# 1-Schematic_STM32F103RCCoreBoard.net
KiCad netlist of a schematic drawn in EasyEDA
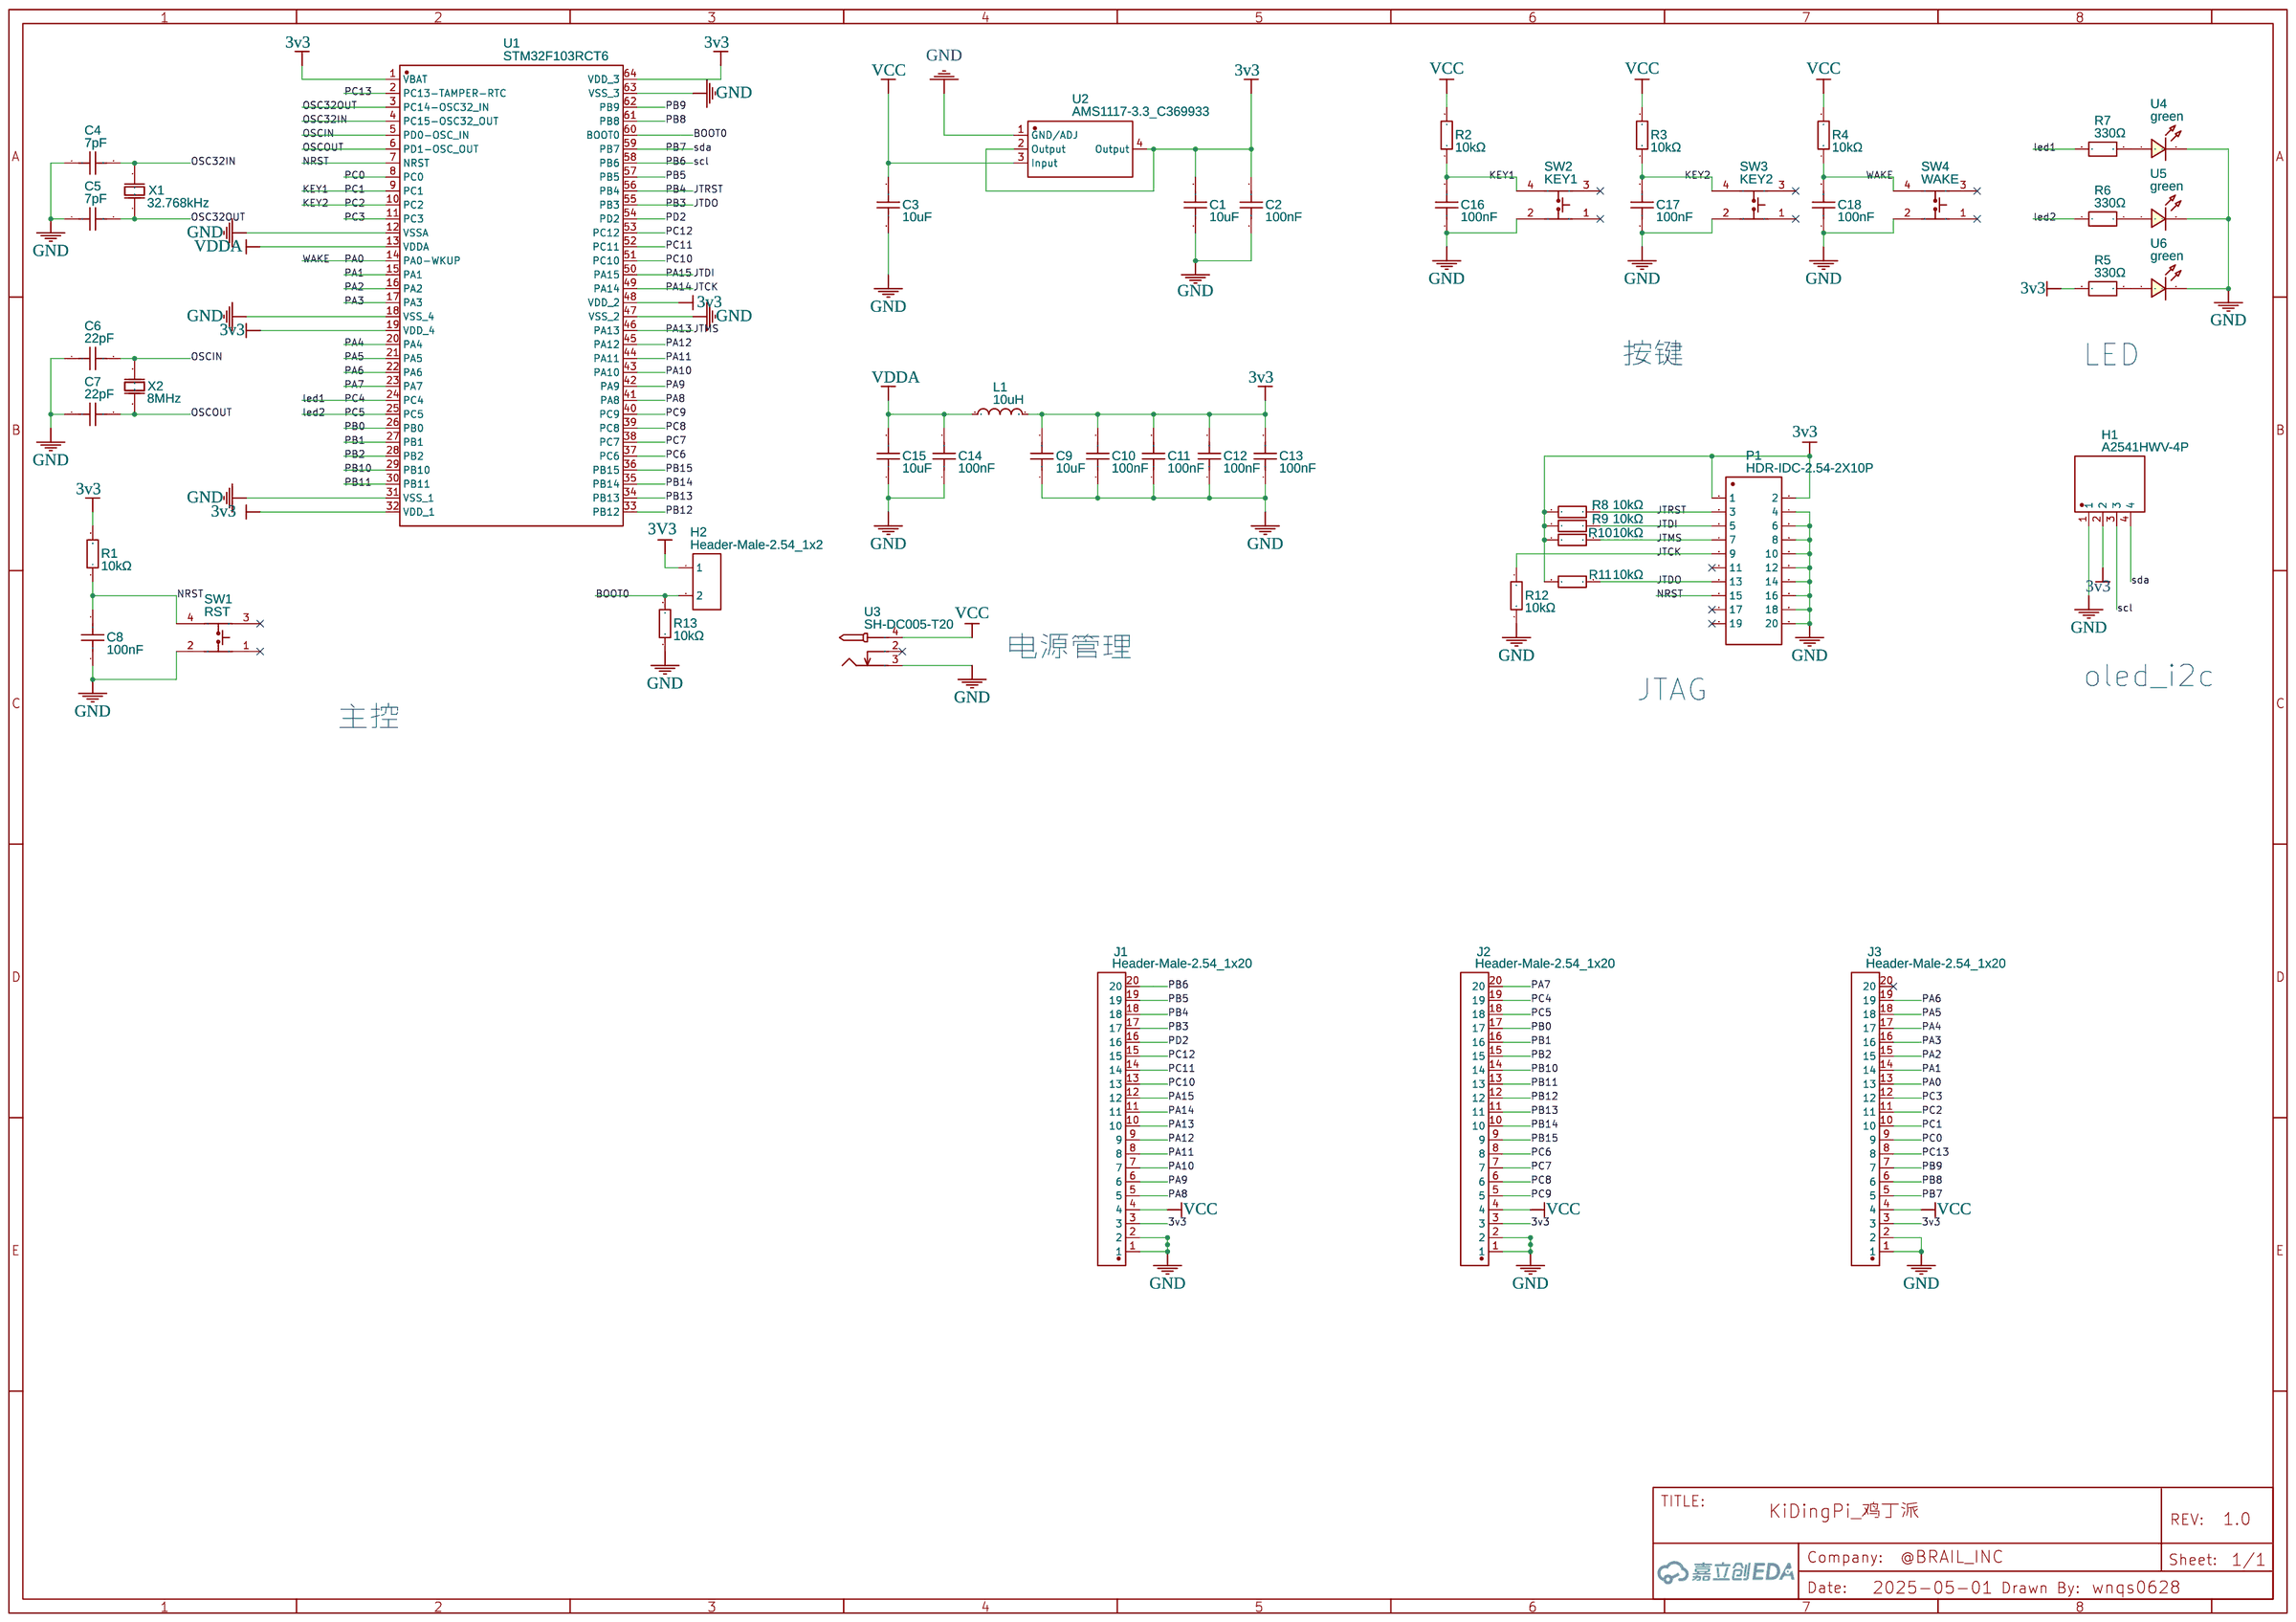
[diagram p0: schematic sheet]

(export (version "E")
  (design (tool "Eeschema 10.0.6"))
  (components
    (comp (ref "C1")
      (value "10uF")
      (fields
        (field (name "Manufacturer Part") "TCC0603X5R106M6R3CT")
        (field (name "Manufacturer") "CCTC(三环)")
      )
      (libsource (lib "") (part "TCC0603X5R106M6R3CT"))
    )
    (comp (ref "C2")
      (value "100nF")
      (fields
        (field (name "Manufacturer Part") "TCC0603X7R104M500CT")
        (field (name "Manufacturer") "CCTC(三环)")
      )
      (libsource (lib "") (part "TCC0603X7R104M500CT"))
    )
    (comp (ref "C3")
      (value "10uF")
      (fields
        (field (name "Manufacturer Part") "TCC0603X5R106M6R3CT")
        (field (name "Manufacturer") "CCTC(三环)")
      )
      (libsource (lib "") (part "TCC0603X5R106M6R3CT"))
    )
    (comp (ref "C4")
      (value "7pF")
      (fields
        (field (name "Manufacturer Part") "GRM1885C1H7R0BA01D")
        (field (name "Manufacturer") "muRata(村田)")
      )
      (libsource (lib "") (part "GRM1885C1H7R0BA01D"))
    )
    (comp (ref "C5")
      (value "7pF")
      (fields
        (field (name "Manufacturer Part") "GRM1885C1H7R0BA01D")
        (field (name "Manufacturer") "muRata(村田)")
      )
      (libsource (lib "") (part "GRM1885C1H7R0BA01D"))
    )
    (comp (ref "C6")
      (value "22pF")
      (fields
        (field (name "Manufacturer Part") "TCC0603COG220K500CT")
        (field (name "Manufacturer") "CCTC(三环)")
      )
      (libsource (lib "") (part "TCC0603COG220K500CT"))
    )
    (comp (ref "C7")
      (value "22pF")
      (fields
        (field (name "Manufacturer Part") "TCC0603COG220K500CT")
        (field (name "Manufacturer") "CCTC(三环)")
      )
      (libsource (lib "") (part "TCC0603COG220K500CT"))
    )
    (comp (ref "C8")
      (value "100nF")
      (fields
        (field (name "Manufacturer Part") "TCC0603Y5V104M500CT")
        (field (name "Manufacturer") "CCTC(三环)")
      )
      (libsource (lib "") (part "TCC0603Y5V104M500CT"))
    )
    (comp (ref "C9")
      (value "10uF")
      (fields
        (field (name "Manufacturer Part") "TCC0603X5R106M6R3CT")
        (field (name "Manufacturer") "CCTC(三环)")
      )
      (libsource (lib "") (part "TCC0603X5R106M6R3CT"))
    )
    (comp (ref "C10")
      (value "100nF")
      (fields
        (field (name "Manufacturer Part") "TCC0603X7R104M500CT")
        (field (name "Manufacturer") "CCTC(三环)")
      )
      (libsource (lib "") (part "TCC0603X7R104M500CT"))
    )
    (comp (ref "C11")
      (value "100nF")
      (fields
        (field (name "Manufacturer Part") "TCC0603X7R104M500CT")
        (field (name "Manufacturer") "CCTC(三环)")
      )
      (libsource (lib "") (part "TCC0603X7R104M500CT"))
    )
    (comp (ref "C12")
      (value "100nF")
      (fields
        (field (name "Manufacturer Part") "TCC0603X7R104M500CT")
        (field (name "Manufacturer") "CCTC(三环)")
      )
      (libsource (lib "") (part "TCC0603X7R104M500CT"))
    )
    (comp (ref "C13")
      (value "100nF")
      (fields
        (field (name "Manufacturer Part") "TCC0603X7R104M500CT")
        (field (name "Manufacturer") "CCTC(三环)")
      )
      (libsource (lib "") (part "TCC0603X7R104M500CT"))
    )
    (comp (ref "C14")
      (value "100nF")
      (fields
        (field (name "Manufacturer Part") "TCC0603X7R104M500CT")
        (field (name "Manufacturer") "CCTC(三环)")
      )
      (libsource (lib "") (part "TCC0603X7R104M500CT"))
    )
    (comp (ref "C15")
      (value "10uF")
      (fields
        (field (name "Manufacturer Part") "TCC0603X5R106M6R3CT")
        (field (name "Manufacturer") "CCTC(三环)")
      )
      (libsource (lib "") (part "TCC0603X5R106M6R3CT"))
    )
    (comp (ref "C16")
      (value "100nF")
      (fields
        (field (name "Manufacturer Part") "TCC0603X7R104M500CT")
        (field (name "Manufacturer") "CCTC(三环)")
      )
      (libsource (lib "") (part "TCC0603X7R104M500CT"))
    )
    (comp (ref "C17")
      (value "100nF")
      (fields
        (field (name "Manufacturer Part") "TCC0603X7R104M500CT")
        (field (name "Manufacturer") "CCTC(三环)")
      )
      (libsource (lib "") (part "TCC0603X7R104M500CT"))
    )
    (comp (ref "C18")
      (value "100nF")
      (fields
        (field (name "Manufacturer Part") "TCC0603X7R104M500CT")
        (field (name "Manufacturer") "CCTC(三环)")
      )
      (libsource (lib "") (part "TCC0603X7R104M500CT"))
    )
    (comp (ref "H1")
      (value "A2541HWV-4P")
      (fields (field (name "Manufacturer") "CJT(长江连接器)"))
      (libsource (lib "") (part "A2541HWV-4P"))
    )
    (comp (ref "H2")
      (value "Header-Male-2.54_1x2")
      (fields
        (field (name "Manufacturer Part") "826629-2")
        (field (name "Manufacturer") "TE Connectivity(泰科电子)")
      )
      (libsource (lib "") (part "Header-Male-2.54_1x2"))
    )
    (comp (ref "J1")
      (value "Header-Male-2.54_1x20")
      (fields (field (name "Manufacturer Part") "2.54-1*20P直针") (field (name "Manufacturer") "BOOMELE(博穆精密)"))
      (libsource (lib "") (part "Header-Male-2.54_1x20"))
    )
    (comp (ref "J2")
      (value "Header-Male-2.54_1x20")
      (fields (field (name "Manufacturer Part") "2.54-1*20P直针") (field (name "Manufacturer") "BOOMELE(博穆精密)"))
      (libsource (lib "") (part "Header-Male-2.54_1x20"))
    )
    (comp (ref "J3")
      (value "Header-Male-2.54_1x20")
      (fields (field (name "Manufacturer Part") "2.54-1*20P直针") (field (name "Manufacturer") "BOOMELE(博穆精密)"))
      (libsource (lib "") (part "Header-Male-2.54_1x20"))
    )
    (comp (ref "L1")
      (value "10uH")
      (fields (field (name "Manufacturer Part") "SFE3015A-100M-F-HF") (field (name "Manufacturer") "DDY(德立)"))
      (libsource (lib "") (part "SFE3015A-100M-F-HF"))
    )
    (comp (ref "P1")
      (value "HDR-IDC-2.54-2X10P")
      (fields (field (name "Manufacturer Part") "2.54-2*10P简牛") (field (name "Manufacturer") "BOOMELE(博穆精密)"))
      (libsource (lib "") (part "HDR-IDC-2.54-2X10P"))
    )
    (comp (ref "R1")
      (value "10kΩ")
      (fields (field (name "Manufacturer Part") "RC0603JR-0710KL") (field (name "Manufacturer") "YAGEO(国巨)"))
      (libsource (lib "") (part "RC0603JR-0710KL_2"))
    )
    (comp (ref "R2")
      (value "10kΩ")
      (fields (field (name "Manufacturer Part") "RC0603JR-0710KL") (field (name "Manufacturer") "YAGEO(国巨)"))
      (libsource (lib "") (part "RC0603JR-0710KL_2"))
    )
    (comp (ref "R3")
      (value "10kΩ")
      (fields (field (name "Manufacturer Part") "RC0603JR-0710KL") (field (name "Manufacturer") "YAGEO(国巨)"))
      (libsource (lib "") (part "RC0603JR-0710KL_2"))
    )
    (comp (ref "R4")
      (value "10kΩ")
      (fields (field (name "Manufacturer Part") "RC0603JR-0710KL") (field (name "Manufacturer") "YAGEO(国巨)"))
      (libsource (lib "") (part "RC0603JR-0710KL_2"))
    )
    (comp (ref "R5")
      (value "330Ω")
      (fields
        (field (name "Manufacturer Part") "TC0325B3300T5F")
        (field (name "Manufacturer") "UNI-ROYAL(厚声)")
      )
      (libsource (lib "") (part "TC0325B3300T5F"))
    )
    (comp (ref "R6")
      (value "330Ω")
      (fields
        (field (name "Manufacturer Part") "TC0325B3300T5F")
        (field (name "Manufacturer") "UNI-ROYAL(厚声)")
      )
      (libsource (lib "") (part "TC0325B3300T5F"))
    )
    (comp (ref "R7")
      (value "330Ω")
      (fields
        (field (name "Manufacturer Part") "TC0325B3300T5F")
        (field (name "Manufacturer") "UNI-ROYAL(厚声)")
      )
      (libsource (lib "") (part "TC0325B3300T5F"))
    )
    (comp (ref "R8")
      (value "10kΩ")
      (fields (field (name "Manufacturer Part") "RC0603JR-0710KL") (field (name "Manufacturer") "YAGEO(国巨)"))
      (libsource (lib "") (part "RC0603JR-0710KL"))
    )
    (comp (ref "R9")
      (value "10kΩ")
      (fields (field (name "Manufacturer Part") "RC0603JR-0710KL") (field (name "Manufacturer") "YAGEO(国巨)"))
      (libsource (lib "") (part "RC0603JR-0710KL"))
    )
    (comp (ref "R10")
      (value "10kΩ")
      (fields (field (name "Manufacturer Part") "RC0603JR-0710KL") (field (name "Manufacturer") "YAGEO(国巨)"))
      (libsource (lib "") (part "RC0603JR-0710KL"))
    )
    (comp (ref "R11")
      (value "10kΩ")
      (fields (field (name "Manufacturer Part") "RC0603JR-0710KL") (field (name "Manufacturer") "YAGEO(国巨)"))
      (libsource (lib "") (part "RC0603JR-0710KL"))
    )
    (comp (ref "R12")
      (value "10kΩ")
      (fields (field (name "Manufacturer Part") "RC0603JR-0710KL") (field (name "Manufacturer") "YAGEO(国巨)"))
      (libsource (lib "") (part "RC0603JR-0710KL_1"))
    )
    (comp (ref "R13")
      (value "10kΩ")
      (fields (field (name "Manufacturer Part") "RC0603JR-0710KL") (field (name "Manufacturer") "YAGEO(国巨)"))
      (libsource (lib "") (part "RC0603JR-0710KL_2"))
    )
    (comp (ref "SW1")
      (value "RST")
      (fields (field (name "Manufacturer Part") "YTS1T0161AWJ00") (field (name "Manufacturer") "YIYUAN(怡远)"))
      (libsource (lib "") (part "YTS1T0161AWJ00"))
    )
    (comp (ref "SW2")
      (value "KEY1")
      (fields (field (name "Manufacturer Part") "YTS1T0161AWJ00") (field (name "Manufacturer") "YIYUAN(怡远)"))
      (libsource (lib "") (part "YTS1T0161AWJ00"))
    )
    (comp (ref "SW3")
      (value "KEY2")
      (fields (field (name "Manufacturer Part") "YTS1T0161AWJ00") (field (name "Manufacturer") "YIYUAN(怡远)"))
      (libsource (lib "") (part "YTS1T0161AWJ00"))
    )
    (comp (ref "SW4")
      (value "WAKE")
      (fields (field (name "Manufacturer Part") "YTS1T0161AWJ00") (field (name "Manufacturer") "YIYUAN(怡远)"))
      (libsource (lib "") (part "YTS1T0161AWJ00"))
    )
    (comp (ref "U1")
      (value "STM32F103RCT6")
      (fields (field (name "Manufacturer") "ST(意法半导体)"))
      (libsource (lib "") (part "STM32F103RCT6"))
    )
    (comp (ref "U2")
      (value "AMS1117-3.3_C369933")
      (fields (field (name "Manufacturer Part") "AMS1117-3.3") (field (name "Manufacturer") "KEXIN(科信)"))
      (libsource (lib "") (part "AMS1117-3.3_C369933"))
    )
    (comp (ref "U3")
      (value "SH-DC005-T20")
      (fields (field (name "Manufacturer") "SHOU HAN(首韩)"))
      (libsource (lib "") (part "SH-DC005-T20"))
    )
    (comp (ref "U4")
      (value "green")
      (fields (field (name "Manufacturer Part") "翠绿色高亮 W0603UG-0.6T"))
      (libsource (lib "") (part "翠绿色高亮 W0603UG-0.6T"))
    )
    (comp (ref "U5")
      (value "green")
      (fields (field (name "Manufacturer Part") "翠绿色高亮 W0603UG-0.6T"))
      (libsource (lib "") (part "翠绿色高亮 W0603UG-0.6T"))
    )
    (comp (ref "U6")
      (value "green")
      (fields (field (name "Manufacturer Part") "翠绿色高亮 W0603UG-0.6T"))
      (libsource (lib "") (part "翠绿色高亮 W0603UG-0.6T"))
    )
    (comp (ref "X1")
      (value "32.768kHz")
      (fields
        (field (name "Manufacturer Part") "XKXEL89CLI-SUAYLC-32.768K")
        (field (name "Manufacturer") "YXC(扬兴晶振)")
      )
      (libsource (lib "") (part "XKXEL89CLI-SUAYLC-32.768K"))
    )
    (comp (ref "X2")
      (value "8MHz")
      (fields (field (name "Manufacturer Part") "X50328MSD2GC") (field (name "Manufacturer") "YXC(扬兴晶振)"))
      (libsource (lib "") (part "X50328MSD2GC_C172361"))
    )
  )
  (nets
    (net (code "1") (name "/BOOT0") (class "Default")
      (node (ref "H2") (pin "2") (pinfunction "2_2") (pintype "unspecified"))
      (node (ref "R13") (pin "2") (pinfunction "2_2") (pintype "input"))
      (node (ref "U1") (pin "60") (pinfunction "BOOT0_60") (pintype "unspecified"))
    )
    (net (code "2") (name "/JTCK") (class "Default")
      (node (ref "J1") (pin "11") (pinfunction "11_11") (pintype "unspecified"))
      (node (ref "P1") (pin "9") (pinfunction "9_9") (pintype "unspecified"))
      (node (ref "R12") (pin "1") (pinfunction "1_1") (pintype "input"))
      (node (ref "U1") (pin "49") (pinfunction "PA14_49") (pintype "unspecified"))
    )
    (net (code "3") (name "/JTDI") (class "Default")
      (node (ref "J1") (pin "12") (pinfunction "12_12") (pintype "unspecified"))
      (node (ref "P1") (pin "5") (pinfunction "5_5") (pintype "unspecified"))
      (node (ref "R9") (pin "1") (pinfunction "1_1") (pintype "input"))
      (node (ref "U1") (pin "50") (pinfunction "PA15_50") (pintype "unspecified"))
    )
    (net (code "4") (name "/JTDO") (class "Default")
      (node (ref "J1") (pin "17") (pinfunction "17_17") (pintype "unspecified"))
      (node (ref "P1") (pin "13") (pinfunction "13_13") (pintype "unspecified"))
      (node (ref "R11") (pin "1") (pinfunction "1_1") (pintype "input"))
      (node (ref "U1") (pin "55") (pinfunction "PB3_55") (pintype "unspecified"))
    )
    (net (code "5") (name "/JTMS") (class "Default")
      (node (ref "J1") (pin "10") (pinfunction "10_10") (pintype "unspecified"))
      (node (ref "P1") (pin "7") (pinfunction "7_7") (pintype "unspecified"))
      (node (ref "R10") (pin "1") (pinfunction "1_1") (pintype "input"))
      (node (ref "U1") (pin "46") (pinfunction "PA13_46") (pintype "unspecified"))
    )
    (net (code "6") (name "/JTRST") (class "Default")
      (node (ref "J1") (pin "18") (pinfunction "18_18") (pintype "unspecified"))
      (node (ref "P1") (pin "3") (pinfunction "3_3") (pintype "unspecified"))
      (node (ref "R8") (pin "1") (pinfunction "1_1") (pintype "input"))
      (node (ref "U1") (pin "56") (pinfunction "PB4_56") (pintype "unspecified"))
    )
    (net (code "7") (name "/KEY1") (class "Default")
      (node (ref "C16") (pin "2") (pinfunction "2_2") (pintype "unspecified"))
      (node (ref "J3") (pin "10") (pinfunction "10_10") (pintype "unspecified"))
      (node (ref "R2") (pin "1") (pinfunction "1_1") (pintype "input"))
      (node (ref "SW2") (pin "4") (pinfunction "4_4") (pintype "unspecified"))
      (node (ref "U1") (pin "9") (pinfunction "PC1_9") (pintype "unspecified"))
    )
    (net (code "8") (name "/KEY2") (class "Default")
      (node (ref "C17") (pin "2") (pinfunction "2_2") (pintype "unspecified"))
      (node (ref "J3") (pin "11") (pinfunction "11_11") (pintype "unspecified"))
      (node (ref "R3") (pin "1") (pinfunction "1_1") (pintype "input"))
      (node (ref "SW3") (pin "4") (pinfunction "4_4") (pintype "unspecified"))
      (node (ref "U1") (pin "10") (pinfunction "PC2_10") (pintype "unspecified"))
    )
    (net (code "9") (name "/NRST") (class "Default")
      (node (ref "C8") (pin "2") (pinfunction "2_2") (pintype "unspecified"))
      (node (ref "P1") (pin "15") (pinfunction "15_15") (pintype "unspecified"))
      (node (ref "R1") (pin "1") (pinfunction "1_1") (pintype "input"))
      (node (ref "SW1") (pin "4") (pinfunction "4_4") (pintype "unspecified"))
      (node (ref "U1") (pin "7") (pinfunction "NRST_7") (pintype "unspecified"))
    )
    (net (code "10") (name "/OSC32IN") (class "Default")
      (node (ref "C4") (pin "2") (pinfunction "2_2") (pintype "unspecified"))
      (node (ref "U1") (pin "4") (pinfunction "PC15-OSC32_OUT_4") (pintype "unspecified"))
      (node (ref "X1") (pin "2") (pinfunction "OSC2_2") (pintype "input"))
    )
    (net (code "11") (name "/OSC32OUT") (class "Default")
      (node (ref "C5") (pin "2") (pinfunction "2_2") (pintype "unspecified"))
      (node (ref "U1") (pin "3") (pinfunction "PC14-OSC32_IN_3") (pintype "unspecified"))
      (node (ref "X1") (pin "1") (pinfunction "OSC1_1") (pintype "input"))
    )
    (net (code "12") (name "/OSCIN") (class "Default")
      (node (ref "C6") (pin "2") (pinfunction "2_2") (pintype "unspecified"))
      (node (ref "U1") (pin "5") (pinfunction "PD0-OSC_IN_5") (pintype "unspecified"))
      (node (ref "X2") (pin "2") (pinfunction "OSC2_2") (pintype "input"))
    )
    (net (code "13") (name "/OSCOUT") (class "Default")
      (node (ref "C7") (pin "2") (pinfunction "2_2") (pintype "unspecified"))
      (node (ref "U1") (pin "6") (pinfunction "PD1-OSC_OUT_6") (pintype "unspecified"))
      (node (ref "X2") (pin "1") (pinfunction "OSC1_1") (pintype "input"))
    )
    (net (code "14") (name "/PA0") (class "Default")
      (node (ref "C18") (pin "2") (pinfunction "2_2") (pintype "unspecified"))
      (node (ref "J3") (pin "13") (pinfunction "13_13") (pintype "unspecified"))
      (node (ref "R4") (pin "1") (pinfunction "1_1") (pintype "input"))
      (node (ref "SW4") (pin "4") (pinfunction "4_4") (pintype "unspecified"))
      (node (ref "U1") (pin "14") (pinfunction "PA0-WKUP_14") (pintype "unspecified"))
    )
    (net (code "15") (name "/PA1") (class "Default")
      (node (ref "J3") (pin "14") (pinfunction "14_14") (pintype "unspecified"))
      (node (ref "U1") (pin "15") (pinfunction "PA1_15") (pintype "unspecified"))
    )
    (net (code "16") (name "/PA2") (class "Default")
      (node (ref "J3") (pin "15") (pinfunction "15_15") (pintype "unspecified"))
      (node (ref "U1") (pin "16") (pinfunction "PA2_16") (pintype "unspecified"))
    )
    (net (code "17") (name "/PA3") (class "Default")
      (node (ref "J3") (pin "16") (pinfunction "16_16") (pintype "unspecified"))
      (node (ref "U1") (pin "17") (pinfunction "PA3_17") (pintype "unspecified"))
    )
    (net (code "18") (name "/PA4") (class "Default")
      (node (ref "J3") (pin "17") (pinfunction "17_17") (pintype "unspecified"))
      (node (ref "U1") (pin "20") (pinfunction "PA4_20") (pintype "unspecified"))
    )
    (net (code "19") (name "/PA5") (class "Default")
      (node (ref "J3") (pin "18") (pinfunction "18_18") (pintype "unspecified"))
      (node (ref "U1") (pin "21") (pinfunction "PA5_21") (pintype "unspecified"))
    )
    (net (code "20") (name "/PA6") (class "Default")
      (node (ref "J3") (pin "19") (pinfunction "19_19") (pintype "unspecified"))
      (node (ref "U1") (pin "22") (pinfunction "PA6_22") (pintype "unspecified"))
    )
    (net (code "21") (name "/PA7") (class "Default")
      (node (ref "J2") (pin "20") (pinfunction "20_20") (pintype "unspecified"))
      (node (ref "U1") (pin "23") (pinfunction "PA7_23") (pintype "unspecified"))
    )
    (net (code "22") (name "/PA8") (class "Default")
      (node (ref "J1") (pin "5") (pinfunction "5_5") (pintype "unspecified"))
      (node (ref "U1") (pin "41") (pinfunction "PA8_41") (pintype "unspecified"))
    )
    (net (code "23") (name "/PA9") (class "Default")
      (node (ref "J1") (pin "6") (pinfunction "6_6") (pintype "unspecified"))
      (node (ref "U1") (pin "42") (pinfunction "PA9_42") (pintype "unspecified"))
    )
    (net (code "24") (name "/PA10") (class "Default")
      (node (ref "J1") (pin "7") (pinfunction "7_7") (pintype "unspecified"))
      (node (ref "U1") (pin "43") (pinfunction "PA10_43") (pintype "unspecified"))
    )
    (net (code "25") (name "/PA11") (class "Default")
      (node (ref "J1") (pin "8") (pinfunction "8_8") (pintype "unspecified"))
      (node (ref "U1") (pin "44") (pinfunction "PA11_44") (pintype "unspecified"))
    )
    (net (code "26") (name "/PA12") (class "Default")
      (node (ref "J1") (pin "9") (pinfunction "9_9") (pintype "unspecified"))
      (node (ref "U1") (pin "45") (pinfunction "PA12_45") (pintype "unspecified"))
    )
    (net (code "27") (name "/PB0") (class "Default")
      (node (ref "J2") (pin "17") (pinfunction "17_17") (pintype "unspecified"))
      (node (ref "U1") (pin "26") (pinfunction "PB0_26") (pintype "unspecified"))
    )
    (net (code "28") (name "/PB1") (class "Default")
      (node (ref "J2") (pin "16") (pinfunction "16_16") (pintype "unspecified"))
      (node (ref "U1") (pin "27") (pinfunction "PB1_27") (pintype "unspecified"))
    )
    (net (code "29") (name "/PB2") (class "Default")
      (node (ref "J2") (pin "15") (pinfunction "15_15") (pintype "unspecified"))
      (node (ref "U1") (pin "28") (pinfunction "PB2_28") (pintype "unspecified"))
    )
    (net (code "30") (name "/PB5") (class "Default")
      (node (ref "J1") (pin "19") (pinfunction "19_19") (pintype "unspecified"))
      (node (ref "U1") (pin "57") (pinfunction "PB5_57") (pintype "unspecified"))
    )
    (net (code "31") (name "/PB6") (class "Default")
      (node (ref "H1") (pin "3") (pinfunction "3_3") (pintype "unspecified"))
      (node (ref "J1") (pin "20") (pinfunction "20_20") (pintype "unspecified"))
      (node (ref "U1") (pin "58") (pinfunction "PB6_58") (pintype "unspecified"))
    )
    (net (code "32") (name "/PB7") (class "Default")
      (node (ref "H1") (pin "4") (pinfunction "4_4") (pintype "unspecified"))
      (node (ref "J3") (pin "5") (pinfunction "5_5") (pintype "unspecified"))
      (node (ref "U1") (pin "59") (pinfunction "PB7_59") (pintype "unspecified"))
    )
    (net (code "33") (name "/PB8") (class "Default")
      (node (ref "J3") (pin "6") (pinfunction "6_6") (pintype "unspecified"))
      (node (ref "U1") (pin "61") (pinfunction "PB8_61") (pintype "unspecified"))
    )
    (net (code "34") (name "/PB9") (class "Default")
      (node (ref "J3") (pin "7") (pinfunction "7_7") (pintype "unspecified"))
      (node (ref "U1") (pin "62") (pinfunction "PB9_62") (pintype "unspecified"))
    )
    (net (code "35") (name "/PB10") (class "Default")
      (node (ref "J2") (pin "14") (pinfunction "14_14") (pintype "unspecified"))
      (node (ref "U1") (pin "29") (pinfunction "PB10_29") (pintype "unspecified"))
    )
    (net (code "36") (name "/PB11") (class "Default")
      (node (ref "J2") (pin "13") (pinfunction "13_13") (pintype "unspecified"))
      (node (ref "U1") (pin "30") (pinfunction "PB11_30") (pintype "unspecified"))
    )
    (net (code "37") (name "/PB12") (class "Default")
      (node (ref "J2") (pin "12") (pinfunction "12_12") (pintype "unspecified"))
      (node (ref "U1") (pin "33") (pinfunction "PB12_33") (pintype "unspecified"))
    )
    (net (code "38") (name "/PB13") (class "Default")
      (node (ref "J2") (pin "11") (pinfunction "11_11") (pintype "unspecified"))
      (node (ref "U1") (pin "34") (pinfunction "PB13_34") (pintype "unspecified"))
    )
    (net (code "39") (name "/PB14") (class "Default")
      (node (ref "J2") (pin "10") (pinfunction "10_10") (pintype "unspecified"))
      (node (ref "U1") (pin "35") (pinfunction "PB14_35") (pintype "unspecified"))
    )
    (net (code "40") (name "/PB15") (class "Default")
      (node (ref "J2") (pin "9") (pinfunction "9_9") (pintype "unspecified"))
      (node (ref "U1") (pin "36") (pinfunction "PB15_36") (pintype "unspecified"))
    )
    (net (code "41") (name "/PC0") (class "Default")
      (node (ref "J3") (pin "9") (pinfunction "9_9") (pintype "unspecified"))
      (node (ref "U1") (pin "8") (pinfunction "PC0_8") (pintype "unspecified"))
    )
    (net (code "42") (name "/PC3") (class "Default")
      (node (ref "J3") (pin "12") (pinfunction "12_12") (pintype "unspecified"))
      (node (ref "U1") (pin "11") (pinfunction "PC3_11") (pintype "unspecified"))
    )
    (net (code "43") (name "/PC4") (class "Default")
      (node (ref "J2") (pin "19") (pinfunction "19_19") (pintype "unspecified"))
      (node (ref "R7") (pin "2") (pinfunction "2_2") (pintype "unspecified"))
      (node (ref "U1") (pin "24") (pinfunction "PC4_24") (pintype "unspecified"))
    )
    (net (code "44") (name "/PC5") (class "Default")
      (node (ref "J2") (pin "18") (pinfunction "18_18") (pintype "unspecified"))
      (node (ref "R6") (pin "2") (pinfunction "2_2") (pintype "unspecified"))
      (node (ref "U1") (pin "25") (pinfunction "PC5_25") (pintype "unspecified"))
    )
    (net (code "45") (name "/PC6") (class "Default")
      (node (ref "J2") (pin "8") (pinfunction "8_8") (pintype "unspecified"))
      (node (ref "U1") (pin "37") (pinfunction "PC6_37") (pintype "unspecified"))
    )
    (net (code "46") (name "/PC7") (class "Default")
      (node (ref "J2") (pin "7") (pinfunction "7_7") (pintype "unspecified"))
      (node (ref "U1") (pin "38") (pinfunction "PC7_38") (pintype "unspecified"))
    )
    (net (code "47") (name "/PC8") (class "Default")
      (node (ref "J2") (pin "6") (pinfunction "6_6") (pintype "unspecified"))
      (node (ref "U1") (pin "39") (pinfunction "PC8_39") (pintype "unspecified"))
    )
    (net (code "48") (name "/PC9") (class "Default")
      (node (ref "J2") (pin "5") (pinfunction "5_5") (pintype "unspecified"))
      (node (ref "U1") (pin "40") (pinfunction "PC9_40") (pintype "unspecified"))
    )
    (net (code "49") (name "/PC10") (class "Default")
      (node (ref "J1") (pin "13") (pinfunction "13_13") (pintype "unspecified"))
      (node (ref "U1") (pin "51") (pinfunction "PC10_51") (pintype "unspecified"))
    )
    (net (code "50") (name "/PC11") (class "Default")
      (node (ref "J1") (pin "14") (pinfunction "14_14") (pintype "unspecified"))
      (node (ref "U1") (pin "52") (pinfunction "PC11_52") (pintype "unspecified"))
    )
    (net (code "51") (name "/PC12") (class "Default")
      (node (ref "J1") (pin "15") (pinfunction "15_15") (pintype "unspecified"))
      (node (ref "U1") (pin "53") (pinfunction "PC12_53") (pintype "unspecified"))
    )
    (net (code "52") (name "/PC13") (class "Default")
      (node (ref "J3") (pin "8") (pinfunction "8_8") (pintype "unspecified"))
      (node (ref "U1") (pin "2") (pinfunction "PC13-TAMPER-RTC_2") (pintype "unspecified"))
    )
    (net (code "53") (name "/PD2") (class "Default")
      (node (ref "J1") (pin "16") (pinfunction "16_16") (pintype "unspecified"))
      (node (ref "U1") (pin "54") (pinfunction "PD2_54") (pintype "unspecified"))
    )
    (net (code "54") (name "3V3") (class "Default")
      (node (ref "H2") (pin "1") (pinfunction "1_1") (pintype "unspecified"))
    )
    (net (code "55") (name "3v3") (class "Default")
      (node (ref "C1") (pin "2") (pinfunction "2_2") (pintype "unspecified"))
      (node (ref "C10") (pin "2") (pinfunction "2_2") (pintype "unspecified"))
      (node (ref "C11") (pin "2") (pinfunction "2_2") (pintype "unspecified"))
      (node (ref "C12") (pin "2") (pinfunction "2_2") (pintype "unspecified"))
      (node (ref "C13") (pin "2") (pinfunction "2_2") (pintype "unspecified"))
      (node (ref "C2") (pin "2") (pinfunction "2_2") (pintype "unspecified"))
      (node (ref "C9") (pin "2") (pinfunction "2_2") (pintype "unspecified"))
      (node (ref "H1") (pin "2") (pinfunction "2_2") (pintype "unspecified"))
      (node (ref "J1") (pin "3") (pinfunction "3_3") (pintype "unspecified"))
      (node (ref "J2") (pin "3") (pinfunction "3_3") (pintype "unspecified"))
      (node (ref "J3") (pin "3") (pinfunction "3_3") (pintype "unspecified"))
      (node (ref "L1") (pin "2") (pinfunction "2_2") (pintype "unspecified"))
      (node (ref "P1") (pin "1") (pinfunction "1_1") (pintype "unspecified"))
      (node (ref "P1") (pin "2") (pinfunction "2_2") (pintype "unspecified"))
      (node (ref "R1") (pin "2") (pinfunction "2_2") (pintype "input"))
      (node (ref "R10") (pin "2") (pinfunction "2_2") (pintype "input"))
      (node (ref "R11") (pin "2") (pinfunction "2_2") (pintype "input"))
      (node (ref "R5") (pin "2") (pinfunction "2_2") (pintype "unspecified"))
      (node (ref "R8") (pin "2") (pinfunction "2_2") (pintype "input"))
      (node (ref "R9") (pin "2") (pinfunction "2_2") (pintype "input"))
      (node (ref "U1") (pin "1") (pinfunction "VBAT_1") (pintype "unspecified"))
      (node (ref "U1") (pin "19") (pinfunction "VDD_4_19") (pintype "unspecified"))
      (node (ref "U1") (pin "32") (pinfunction "VDD_1_32") (pintype "unspecified"))
      (node (ref "U1") (pin "48") (pinfunction "VDD_2_48") (pintype "unspecified"))
      (node (ref "U1") (pin "64") (pinfunction "VDD_3_64") (pintype "unspecified"))
      (node (ref "U2") (pin "2") (pinfunction "Output_2") (pintype "unspecified"))
      (node (ref "U2") (pin "4") (pinfunction "Output_4") (pintype "unspecified"))
    )
    (net (code "56") (name "GND") (class "Default")
      (node (ref "C1") (pin "1") (pinfunction "1_1") (pintype "unspecified"))
      (node (ref "C10") (pin "1") (pinfunction "1_1") (pintype "unspecified"))
      (node (ref "C11") (pin "1") (pinfunction "1_1") (pintype "unspecified"))
      (node (ref "C12") (pin "1") (pinfunction "1_1") (pintype "unspecified"))
      (node (ref "C13") (pin "1") (pinfunction "1_1") (pintype "unspecified"))
      (node (ref "C14") (pin "1") (pinfunction "1_1") (pintype "unspecified"))
      (node (ref "C15") (pin "1") (pinfunction "1_1") (pintype "unspecified"))
      (node (ref "C16") (pin "1") (pinfunction "1_1") (pintype "unspecified"))
      (node (ref "C17") (pin "1") (pinfunction "1_1") (pintype "unspecified"))
      (node (ref "C18") (pin "1") (pinfunction "1_1") (pintype "unspecified"))
      (node (ref "C2") (pin "1") (pinfunction "1_1") (pintype "unspecified"))
      (node (ref "C3") (pin "1") (pinfunction "1_1") (pintype "unspecified"))
      (node (ref "C4") (pin "1") (pinfunction "1_1") (pintype "unspecified"))
      (node (ref "C5") (pin "1") (pinfunction "1_1") (pintype "unspecified"))
      (node (ref "C6") (pin "1") (pinfunction "1_1") (pintype "unspecified"))
      (node (ref "C7") (pin "1") (pinfunction "1_1") (pintype "unspecified"))
      (node (ref "C8") (pin "1") (pinfunction "1_1") (pintype "unspecified"))
      (node (ref "C9") (pin "1") (pinfunction "1_1") (pintype "unspecified"))
      (node (ref "H1") (pin "1") (pinfunction "1_1") (pintype "unspecified"))
      (node (ref "J1") (pin "1") (pinfunction "1_1") (pintype "unspecified"))
      (node (ref "J1") (pin "2") (pinfunction "2_2") (pintype "unspecified"))
      (node (ref "J2") (pin "1") (pinfunction "1_1") (pintype "unspecified"))
      (node (ref "J2") (pin "2") (pinfunction "2_2") (pintype "unspecified"))
      (node (ref "J3") (pin "1") (pinfunction "1_1") (pintype "unspecified"))
      (node (ref "J3") (pin "2") (pinfunction "2_2") (pintype "unspecified"))
      (node (ref "P1") (pin "10") (pinfunction "10_10") (pintype "unspecified"))
      (node (ref "P1") (pin "12") (pinfunction "12_12") (pintype "unspecified"))
      (node (ref "P1") (pin "14") (pinfunction "14_14") (pintype "unspecified"))
      (node (ref "P1") (pin "16") (pinfunction "16_16") (pintype "unspecified"))
      (node (ref "P1") (pin "18") (pinfunction "18_18") (pintype "unspecified"))
      (node (ref "P1") (pin "20") (pinfunction "20_20") (pintype "unspecified"))
      (node (ref "P1") (pin "4") (pinfunction "4_4") (pintype "unspecified"))
      (node (ref "P1") (pin "6") (pinfunction "6_6") (pintype "unspecified"))
      (node (ref "P1") (pin "8") (pinfunction "8_8") (pintype "unspecified"))
      (node (ref "R12") (pin "2") (pinfunction "2_2") (pintype "input"))
      (node (ref "R13") (pin "1") (pinfunction "1_1") (pintype "input"))
      (node (ref "SW1") (pin "2") (pinfunction "2_2") (pintype "unspecified"))
      (node (ref "SW2") (pin "2") (pinfunction "2_2") (pintype "unspecified"))
      (node (ref "SW3") (pin "2") (pinfunction "2_2") (pintype "unspecified"))
      (node (ref "SW4") (pin "2") (pinfunction "2_2") (pintype "unspecified"))
      (node (ref "U1") (pin "12") (pinfunction "VSSA_12") (pintype "unspecified"))
      (node (ref "U1") (pin "18") (pinfunction "VSS_4_18") (pintype "unspecified"))
      (node (ref "U1") (pin "31") (pinfunction "VSS_1_31") (pintype "unspecified"))
      (node (ref "U1") (pin "47") (pinfunction "VSS_2_47") (pintype "unspecified"))
      (node (ref "U1") (pin "63") (pinfunction "VSS_3_63") (pintype "unspecified"))
      (node (ref "U2") (pin "1") (pinfunction "GND/ADJ_1") (pintype "unspecified"))
      (node (ref "U3") (pin "3") (pinfunction "3_3") (pintype "unspecified"))
      (node (ref "U4") (pin "2") (pinfunction "-_2") (pintype "unspecified"))
      (node (ref "U5") (pin "2") (pinfunction "-_2") (pintype "unspecified"))
      (node (ref "U6") (pin "2") (pinfunction "-_2") (pintype "unspecified"))
    )
    (net (code "57") (name "Net-(U4-+)") (class "Default")
      (node (ref "R7") (pin "1") (pinfunction "1_1") (pintype "unspecified"))
      (node (ref "U4") (pin "1") (pinfunction "+_1") (pintype "unspecified"))
    )
    (net (code "58") (name "Net-(U5-+)") (class "Default")
      (node (ref "R6") (pin "1") (pinfunction "1_1") (pintype "unspecified"))
      (node (ref "U5") (pin "1") (pinfunction "+_1") (pintype "unspecified"))
    )
    (net (code "59") (name "Net-(U6-+)") (class "Default")
      (node (ref "R5") (pin "1") (pinfunction "1_1") (pintype "unspecified"))
      (node (ref "U6") (pin "1") (pinfunction "+_1") (pintype "unspecified"))
    )
    (net (code "60") (name "VCC") (class "Default")
      (node (ref "C3") (pin "2") (pinfunction "2_2") (pintype "unspecified"))
      (node (ref "J1") (pin "4") (pinfunction "4_4") (pintype "unspecified"))
      (node (ref "J2") (pin "4") (pinfunction "4_4") (pintype "unspecified"))
      (node (ref "J3") (pin "4") (pinfunction "4_4") (pintype "unspecified"))
      (node (ref "R2") (pin "2") (pinfunction "2_2") (pintype "input"))
      (node (ref "R3") (pin "2") (pinfunction "2_2") (pintype "input"))
      (node (ref "R4") (pin "2") (pinfunction "2_2") (pintype "input"))
      (node (ref "U2") (pin "3") (pinfunction "Input_3") (pintype "unspecified"))
      (node (ref "U3") (pin "4") (pinfunction "4_4") (pintype "unspecified"))
    )
    (net (code "61") (name "VDDA") (class "Default")
      (node (ref "C14") (pin "2") (pinfunction "2_2") (pintype "unspecified"))
      (node (ref "C15") (pin "2") (pinfunction "2_2") (pintype "unspecified"))
      (node (ref "L1") (pin "1") (pinfunction "1_1") (pintype "unspecified"))
      (node (ref "U1") (pin "13") (pinfunction "VDDA_13") (pintype "unspecified"))
    )
    (net (code "62") (name "unconnected-(J3-Pad20)") (class "Default")
      (node (ref "J3") (pin "20") (pinfunction "20_20") (pintype "unspecified+no_connect"))
    )
    (net (code "63") (name "unconnected-(P1-Pad11)") (class "Default")
      (node (ref "P1") (pin "11") (pinfunction "11_11") (pintype "unspecified+no_connect"))
    )
    (net (code "64") (name "unconnected-(P1-Pad17)") (class "Default")
      (node (ref "P1") (pin "17") (pinfunction "17_17") (pintype "unspecified+no_connect"))
    )
    (net (code "65") (name "unconnected-(P1-Pad19)") (class "Default")
      (node (ref "P1") (pin "19") (pinfunction "19_19") (pintype "unspecified+no_connect"))
    )
    (net (code "66") (name "unconnected-(SW1-Pad1)") (class "Default")
      (node (ref "SW1") (pin "1") (pinfunction "1_1") (pintype "unspecified+no_connect"))
    )
    (net (code "67") (name "unconnected-(SW1-Pad3)") (class "Default")
      (node (ref "SW1") (pin "3") (pinfunction "3_3") (pintype "unspecified+no_connect"))
    )
    (net (code "68") (name "unconnected-(SW2-Pad1)") (class "Default")
      (node (ref "SW2") (pin "1") (pinfunction "1_1") (pintype "unspecified+no_connect"))
    )
    (net (code "69") (name "unconnected-(SW2-Pad3)") (class "Default")
      (node (ref "SW2") (pin "3") (pinfunction "3_3") (pintype "unspecified+no_connect"))
    )
    (net (code "70") (name "unconnected-(SW3-Pad1)") (class "Default")
      (node (ref "SW3") (pin "1") (pinfunction "1_1") (pintype "unspecified+no_connect"))
    )
    (net (code "71") (name "unconnected-(SW3-Pad3)") (class "Default")
      (node (ref "SW3") (pin "3") (pinfunction "3_3") (pintype "unspecified+no_connect"))
    )
    (net (code "72") (name "unconnected-(SW4-Pad1)") (class "Default")
      (node (ref "SW4") (pin "1") (pinfunction "1_1") (pintype "unspecified+no_connect"))
    )
    (net (code "73") (name "unconnected-(SW4-Pad3)") (class "Default")
      (node (ref "SW4") (pin "3") (pinfunction "3_3") (pintype "unspecified+no_connect"))
    )
    (net (code "74") (name "unconnected-(U3-Pad2)") (class "Default")
      (node (ref "U3") (pin "2") (pinfunction "2_2") (pintype "unspecified+no_connect"))
    )
  )
)
